# ESP_PGMR.net
KiCad netlist of a schematic drawn in EAGLE
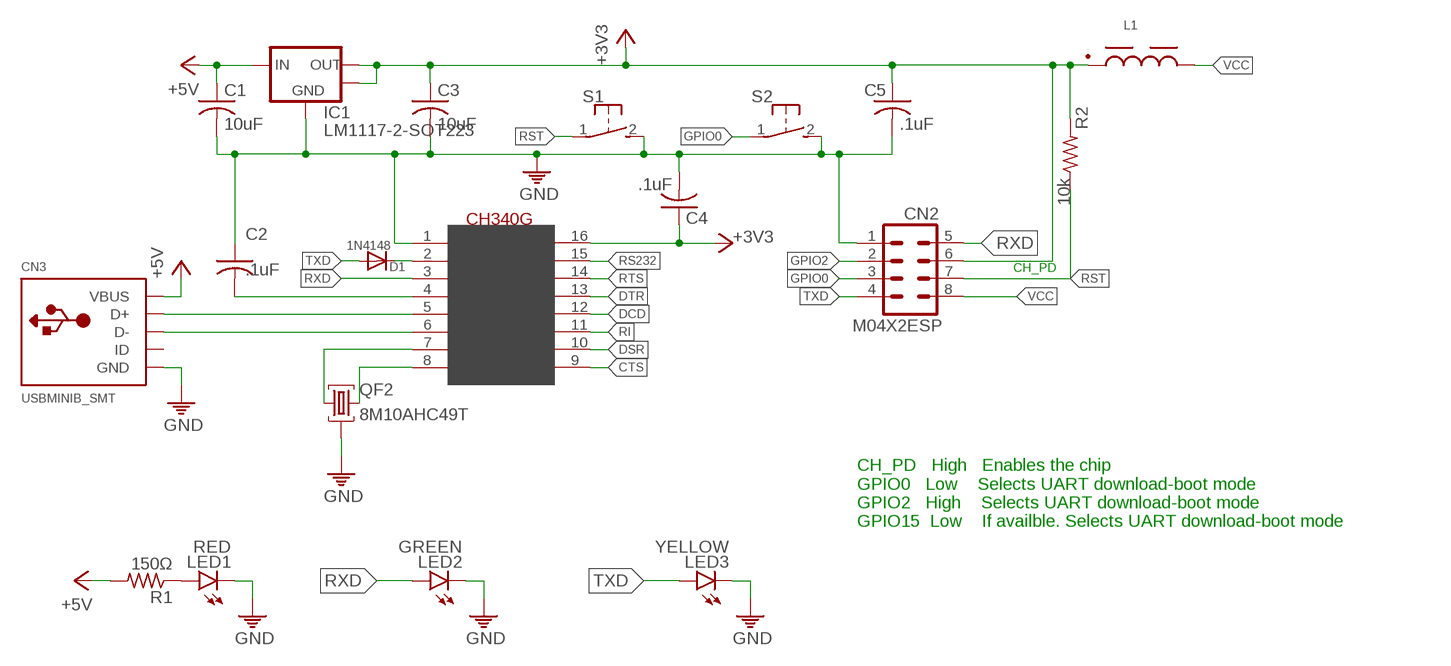
[diagram p0: schematic, sheet 1]

(export (version "E")
  (design (tool "Eeschema 10.0.6"))
  (components
    (comp (ref "C1")
      (value "10uF")
      (footprint "eagle-import:C0805")
      (libsource (lib "eagle-import") (part "C-USC0805"))
    )
    (comp (ref "C2")
      (value ".1uF")
      (footprint "eagle-import:C0805")
      (libsource (lib "eagle-import") (part "C-USC0805"))
    )
    (comp (ref "C3")
      (value "10uF")
      (footprint "eagle-import:C0805")
      (libsource (lib "eagle-import") (part "C-USC0805"))
    )
    (comp (ref "C4")
      (value ".1uF")
      (footprint "eagle-import:C0805")
      (libsource (lib "eagle-import") (part "C-USC0805"))
    )
    (comp (ref "C5")
      (value ".1uF")
      (footprint "eagle-import:C0805")
      (libsource (lib "eagle-import") (part "C-USC0805"))
    )
    (comp (ref "CN2")
      (value "M04X2ESP")
      (footprint "eagle-import:2X04-ESP")
      (libsource (lib "eagle-import") (part "M04X2ESP"))
    )
    (comp (ref "CN3")
      (value "USBMINIB_SMT")
      (footprint "eagle-import:USB_MINI_B")
      (libsource (lib "eagle-import") (part "USBMINIB_SMT"))
    )
    (comp (ref "D1")
      (value "1N4148")
      (footprint "eagle-import:SOD-123")
      (libsource (lib "eagle-import") (part "DIODE_SOD-123"))
    )
    (comp (ref "IC1")
      (value "LM1117-2-SOT223")
      (footprint "eagle-import:SOT-223-3")
      (libsource (lib "eagle-import") (part "LM1117-2-SOT223"))
    )
    (comp (ref "IC2")
      (value "CH340G")
      (footprint "eagle-import:SOIC16")
      (libsource (lib "eagle-import") (part "CH340G"))
    )
    (comp (ref "L1")
      (value "WE-CBA_0805_782851102_WB/HS")
      (footprint "eagle-import:WE-CBA_0805(W=3)")
      (libsource (lib "eagle-import") (part "WE-CBA_0805_WB/HS_782851102"))
    )
    (comp (ref "LED1")
      (value "RED")
      (footprint "eagle-import:CHIPLED_1206")
      (libsource (lib "eagle-import") (part "LEDCHIPLED_1206"))
    )
    (comp (ref "LED2")
      (value "GREEN")
      (footprint "eagle-import:CHIPLED_1206")
      (libsource (lib "eagle-import") (part "LEDCHIPLED_1206"))
    )
    (comp (ref "LED3")
      (value "YELLOW")
      (footprint "eagle-import:CHIPLED_1206")
      (libsource (lib "eagle-import") (part "LEDCHIPLED_1206"))
    )
    (comp (ref "QF2")
      (value "8M10AHC49T")
      (footprint "eagle-import:HC49U")
      (libsource (lib "eagle-import") (part "8M10AHC49T"))
    )
    (comp (ref "R1")
      (value "150Ω")
      (footprint "eagle-import:M0805")
      (libsource (lib "eagle-import") (part "resistor_348_R-US_M0805"))
    )
    (comp (ref "R2")
      (value "10k")
      (footprint "eagle-import:R0805")
      (libsource (lib "eagle-import") (part "R-US_R0805"))
    )
    (comp (ref "S1")
      (value "MOMENTARY-SWITCH-SPST-PTH-6.0X6.0-5MM")
      (footprint "eagle-import:TACTILE_SWITCH_PTH_6.0X6.0-5MM")
      (libsource (lib "eagle-import") (part "MOMENTARY-SWITCH-SPST-PTH-6.0X6.0-5MM"))
    )
    (comp (ref "S2")
      (value "MOMENTARY-SWITCH-SPST-PTH-6.0X6.0-5MM")
      (footprint "eagle-import:TACTILE_SWITCH_PTH_6.0X6.0-5MM")
      (libsource (lib "eagle-import") (part "MOMENTARY-SWITCH-SPST-PTH-6.0X6.0-5MM"))
    )
  )
  (nets
    (net (code "1") (name "+3V3") (class "Default")
      (node (ref "C3") (pin "1") (pinfunction "1_1") (pintype "passive"))
      (node (ref "C4") (pin "1") (pinfunction "1_1") (pintype "passive"))
      (node (ref "C5") (pin "1") (pinfunction "1_1") (pintype "passive"))
      (node (ref "CN2") (pin "6") (pinfunction "6_6") (pintype "passive"))
      (node (ref "IC1") (pin "2") (pinfunction "VOUT_2") (pintype "bidirectional"))
      (node (ref "IC1") (pin "4") (pinfunction "HEATSINK_4") (pintype "bidirectional"))
      (node (ref "IC2") (pin "16") (pinfunction "VCC_16") (pintype "bidirectional"))
      (node (ref "L1") (pin "1") (pinfunction "1_1") (pintype "passive"))
      (node (ref "R2") (pin "2") (pinfunction "2_2") (pintype "passive"))
    )
    (net (code "2") (name "+5V") (class "Default")
      (node (ref "C1") (pin "1") (pinfunction "1_1") (pintype "passive"))
      (node (ref "CN3") (pin "VBUS") (pinfunction "VBUS_VBUS") (pintype "power_in"))
      (node (ref "IC1") (pin "3") (pinfunction "VIN_3") (pintype "bidirectional"))
      (node (ref "R1") (pin "2") (pinfunction "2_2") (pintype "passive"))
    )
    (net (code "3") (name "CTS") (class "Default")
      (node (ref "IC2") (pin "9") (pinfunction "CTS_9") (pintype "bidirectional"))
    )
    (net (code "4") (name "DCD") (class "Default")
      (node (ref "IC2") (pin "12") (pinfunction "DCD_12") (pintype "bidirectional"))
    )
    (net (code "5") (name "DSR") (class "Default")
      (node (ref "IC2") (pin "10") (pinfunction "DSR_10") (pintype "bidirectional"))
    )
    (net (code "6") (name "DTR") (class "Default")
      (node (ref "IC2") (pin "13") (pinfunction "DTR_13") (pintype "bidirectional"))
    )
    (net (code "7") (name "GND") (class "Default")
      (node (ref "C1") (pin "2") (pinfunction "2_2") (pintype "passive"))
      (node (ref "C2") (pin "1") (pinfunction "1_1") (pintype "passive"))
      (node (ref "C3") (pin "2") (pinfunction "2_2") (pintype "passive"))
      (node (ref "C4") (pin "2") (pinfunction "2_2") (pintype "passive"))
      (node (ref "C5") (pin "2") (pinfunction "2_2") (pintype "passive"))
      (node (ref "CN2") (pin "1") (pinfunction "1_1") (pintype "passive"))
      (node (ref "CN3") (pin "GND") (pinfunction "GND_GND") (pintype "power_in"))
      (node (ref "CN3") (pin "GND1") (pinfunction "GND_GND1") (pintype "power_in"))
      (node (ref "CN3") (pin "GND2") (pinfunction "GND_GND2") (pintype "power_in"))
      (node (ref "CN3") (pin "GND3") (pinfunction "GND_GND3") (pintype "power_in"))
      (node (ref "CN3") (pin "GND4") (pinfunction "GND_GND4") (pintype "power_in"))
      (node (ref "IC1") (pin "1") (pinfunction "GND_1") (pintype "bidirectional"))
      (node (ref "IC2") (pin "1") (pinfunction "GND_1") (pintype "bidirectional"))
      (node (ref "LED1") (pin "C") (pinfunction "C_C") (pintype "passive"))
      (node (ref "LED2") (pin "C") (pinfunction "C_C") (pintype "passive"))
      (node (ref "LED3") (pin "C") (pinfunction "C_C") (pintype "passive"))
      (node (ref "QF2") (pin "2") (pinfunction "2_2") (pintype "passive"))
      (node (ref "S1") (pin "2") (pinfunction "S_2") (pintype "passive"))
      (node (ref "S2") (pin "2") (pinfunction "S_2") (pintype "passive"))
    )
    (net (code "8") (name "GPIO0") (class "Default")
      (node (ref "CN2") (pin "3") (pinfunction "3_3") (pintype "passive"))
      (node (ref "S2") (pin "1") (pinfunction "P_1") (pintype "passive"))
    )
    (net (code "9") (name "GPIO2") (class "Default")
      (node (ref "CN2") (pin "2") (pinfunction "2_2") (pintype "passive"))
    )
    (net (code "10") (name "Net-(IC2-D+)") (class "Default")
      (node (ref "CN3") (pin "D+") (pinfunction "D+_D+") (pintype "bidirectional"))
      (node (ref "IC2") (pin "5") (pinfunction "D+_5") (pintype "bidirectional"))
    )
    (net (code "11") (name "Net-(IC2-D-)") (class "Default")
      (node (ref "CN3") (pin "D-") (pinfunction "D-_D-") (pintype "bidirectional"))
      (node (ref "IC2") (pin "6") (pinfunction "D-_6") (pintype "bidirectional"))
    )
    (net (code "12") (name "Net-(IC2-TX)") (class "Default")
      (node (ref "D1") (pin "C") (pinfunction "C_C") (pintype "passive"))
      (node (ref "IC2") (pin "2") (pinfunction "TX_2") (pintype "bidirectional"))
    )
    (net (code "13") (name "Net-(IC2-V3)") (class "Default")
      (node (ref "C2") (pin "2") (pinfunction "2_2") (pintype "passive"))
      (node (ref "IC2") (pin "4") (pinfunction "V3_4") (pintype "bidirectional"))
    )
    (net (code "14") (name "Net-(IC2-XI)") (class "Default")
      (node (ref "IC2") (pin "7") (pinfunction "XI_7") (pintype "bidirectional"))
      (node (ref "QF2") (pin "1") (pinfunction "1_1") (pintype "passive"))
    )
    (net (code "15") (name "Net-(IC2-XO)") (class "Default")
      (node (ref "IC2") (pin "8") (pinfunction "XO_8") (pintype "bidirectional"))
      (node (ref "QF2") (pin "3") (pinfunction "3_3") (pintype "passive"))
    )
    (net (code "16") (name "Net-(LED1-PadA)") (class "Default")
      (node (ref "LED1") (pin "A") (pinfunction "A_A") (pintype "passive"))
      (node (ref "R1") (pin "1") (pinfunction "1_1") (pintype "passive"))
    )
    (net (code "17") (name "RI") (class "Default")
      (node (ref "IC2") (pin "11") (pinfunction "RI_11") (pintype "bidirectional"))
    )
    (net (code "18") (name "RS232") (class "Default")
      (node (ref "IC2") (pin "15") (pinfunction "RS232_15") (pintype "bidirectional"))
    )
    (net (code "19") (name "RST") (class "Default")
      (node (ref "CN2") (pin "7") (pinfunction "7_7") (pintype "passive"))
      (node (ref "R2") (pin "1") (pinfunction "1_1") (pintype "passive"))
      (node (ref "S1") (pin "1") (pinfunction "P_1") (pintype "passive"))
    )
    (net (code "20") (name "RTS") (class "Default")
      (node (ref "IC2") (pin "14") (pinfunction "RTS_14") (pintype "bidirectional"))
    )
    (net (code "21") (name "RXD") (class "Default")
      (node (ref "CN2") (pin "5") (pinfunction "5_5") (pintype "passive"))
      (node (ref "IC2") (pin "3") (pinfunction "RX_3") (pintype "bidirectional"))
      (node (ref "LED2") (pin "A") (pinfunction "A_A") (pintype "passive"))
    )
    (net (code "22") (name "TXD") (class "Default")
      (node (ref "CN2") (pin "4") (pinfunction "4_4") (pintype "passive"))
      (node (ref "D1") (pin "A") (pinfunction "A_A") (pintype "passive"))
      (node (ref "LED3") (pin "A") (pinfunction "A_A") (pintype "passive"))
    )
    (net (code "23") (name "VCC") (class "Default")
      (node (ref "CN2") (pin "8") (pinfunction "8_8") (pintype "passive"))
      (node (ref "L1") (pin "2") (pinfunction "2_2") (pintype "passive"))
    )
    (net (code "24") (name "unconnected-(CN3-PadID)") (class "Default")
      (node (ref "CN3") (pin "ID") (pinfunction "ID_ID") (pintype "bidirectional"))
    )
  )
)
